# MicroMod_Asset_Tracker_Firmware_Update_T.net
KiCad netlist of a schematic drawn in EAGLE
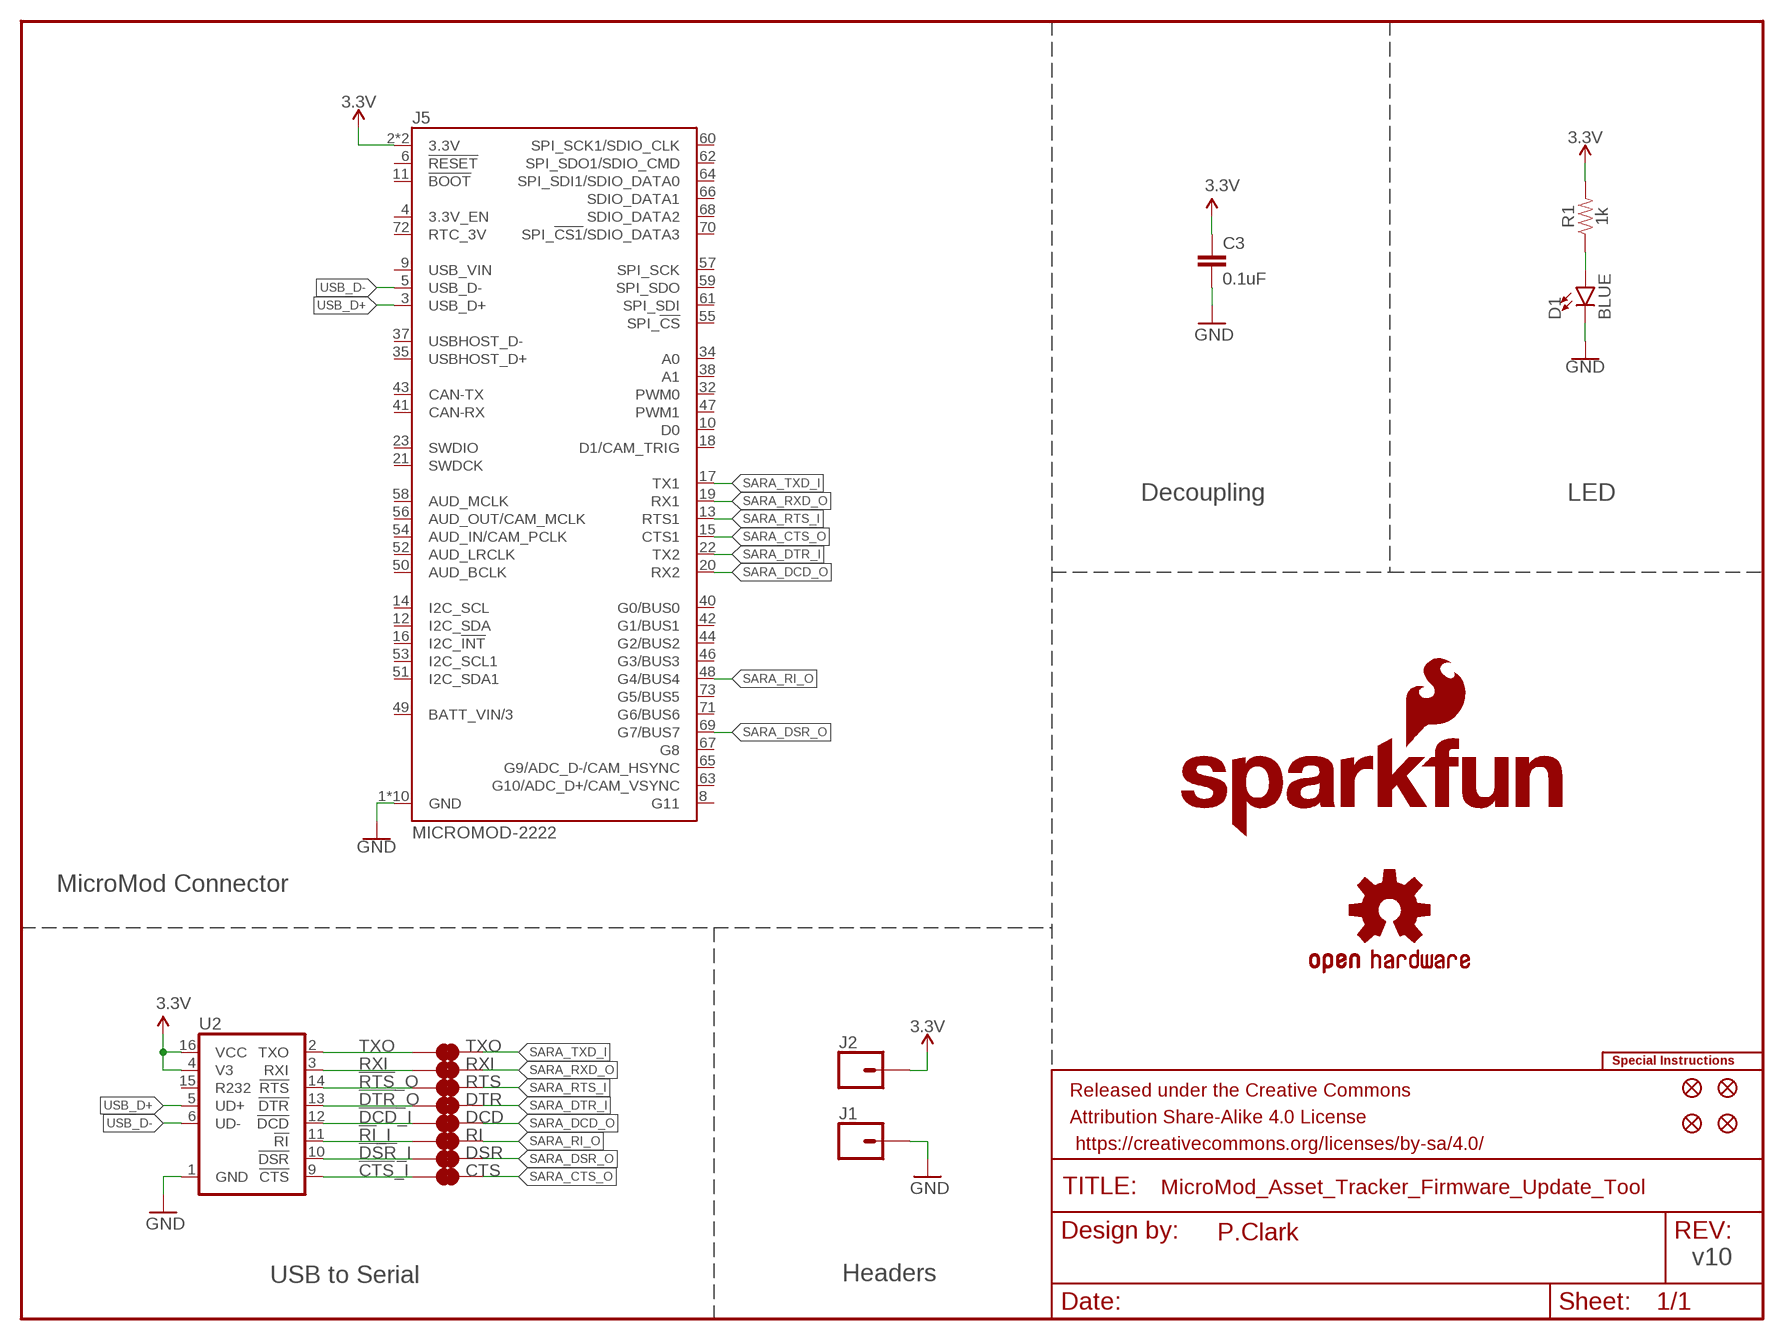
[diagram p0: schematic, sheet 1]

(export (version "E")
  (design (tool "Eeschema 10.0.6"))
  (components
    (comp (ref "C3")
      (value "0.1uF")
      (footprint "eagle-import:0603")
      (libsource (lib "eagle-import") (part "0.1UF-0603-25V-5%"))
    )
    (comp (ref "CTS")
      (value "JUMPER-COMBO_2_NC_TRACE")
      (footprint "eagle-import:COMBO-JUMPER_2_NC_TRACE")
      (libsource (lib "eagle-import") (part "JUMPER-COMBO_2_NC_TRACE"))
    )
    (comp (ref "D1")
      (value "BLUE")
      (footprint "eagle-import:LED-0603")
      (libsource (lib "eagle-import") (part "LED-BLUE0603"))
    )
    (comp (ref "DCD")
      (value "JUMPER-COMBO_2_NC_TRACE")
      (footprint "eagle-import:COMBO-JUMPER_2_NC_TRACE")
      (libsource (lib "eagle-import") (part "JUMPER-COMBO_2_NC_TRACE"))
    )
    (comp (ref "DSR")
      (value "JUMPER-COMBO_2_NC_TRACE")
      (footprint "eagle-import:COMBO-JUMPER_2_NC_TRACE")
      (libsource (lib "eagle-import") (part "JUMPER-COMBO_2_NC_TRACE"))
    )
    (comp (ref "DTR")
      (value "JUMPER-COMBO_2_NC_TRACE")
      (footprint "eagle-import:COMBO-JUMPER_2_NC_TRACE")
      (libsource (lib "eagle-import") (part "JUMPER-COMBO_2_NC_TRACE"))
    )
    (comp (ref "FRAME1")
      (value "FRAME-LETTER")
      (footprint "eagle-import:CREATIVE_COMMONS")
      (libsource (lib "eagle-import") (part "FRAME-LETTER"))
    )
    (comp (ref "J1")
      (value "CONN_01PTH_NO_SILK_YES_STOP")
      (footprint "eagle-import:1X01_NO_SILK")
      (libsource (lib "eagle-import") (part "CONN_01PTH_NO_SILK_YES_STOP"))
    )
    (comp (ref "J2")
      (value "CONN_01PTH_NO_SILK_YES_STOP")
      (footprint "eagle-import:1X01_NO_SILK")
      (libsource (lib "eagle-import") (part "CONN_01PTH_NO_SILK_YES_STOP"))
    )
    (comp (ref "J5")
      (value "MICROMOD-2222")
      (footprint "eagle-import:M.2-CARD-E-22")
      (libsource (lib "eagle-import") (part "MICROMOD-2222"))
    )
    (comp (ref "JP3")
      (value "FIDUCIAL1X2")
      (footprint "eagle-import:FIDUCIAL-1X2")
      (libsource (lib "eagle-import") (part "FIDUCIAL1X2"))
    )
    (comp (ref "JP4")
      (value "FIDUCIAL1X2")
      (footprint "eagle-import:FIDUCIAL-1X2")
      (libsource (lib "eagle-import") (part "FIDUCIAL1X2"))
    )
    (comp (ref "JP5")
      (value "FIDUCIAL1X2")
      (footprint "eagle-import:FIDUCIAL-1X2")
      (libsource (lib "eagle-import") (part "FIDUCIAL1X2"))
    )
    (comp (ref "JP6")
      (value "FIDUCIAL1X2")
      (footprint "eagle-import:FIDUCIAL-1X2")
      (libsource (lib "eagle-import") (part "FIDUCIAL1X2"))
    )
    (comp (ref "LOGO1")
      (value "OSHW-LOGOMINI")
      (footprint "eagle-import:OSHW-LOGO-MINI")
      (libsource (lib "eagle-import") (part "OSHW-LOGOMINI"))
    )
    (comp (ref "LOGO2")
      (value "SPECIAL_INSTRUCTIONS-ORDERING")
      (footprint "eagle-import:ORDERING_INSTRUCTIONS")
      (libsource (lib "eagle-import") (part "SPECIAL_INSTRUCTIONS-ORDERING"))
    )
    (comp (ref "LOGO3")
      (value "SFE_LOGO_NAME_FLAME.1_INCH")
      (footprint "eagle-import:SFE_LOGO_NAME_FLAME_.1")
      (libsource (lib "eagle-import") (part "SFE_LOGO_NAME_FLAME.1_INCH"))
    )
    (comp (ref "R1")
      (value "1k")
      (footprint "eagle-import:0603")
      (libsource (lib "eagle-import") (part "1KOHM-0603-1/10W-1%"))
    )
    (comp (ref "RI")
      (value "JUMPER-COMBO_2_NC_TRACE")
      (footprint "eagle-import:COMBO-JUMPER_2_NC_TRACE")
      (libsource (lib "eagle-import") (part "JUMPER-COMBO_2_NC_TRACE"))
    )
    (comp (ref "RTS")
      (value "JUMPER-COMBO_2_NC_TRACE")
      (footprint "eagle-import:COMBO-JUMPER_2_NC_TRACE")
      (libsource (lib "eagle-import") (part "JUMPER-COMBO_2_NC_TRACE"))
    )
    (comp (ref "RXI")
      (value "JUMPER-COMBO_2_NC_TRACE")
      (footprint "eagle-import:COMBO-JUMPER_2_NC_TRACE")
      (libsource (lib "eagle-import") (part "JUMPER-COMBO_2_NC_TRACE"))
    )
    (comp (ref "TXO")
      (value "JUMPER-COMBO_2_NC_TRACE")
      (footprint "eagle-import:COMBO-JUMPER_2_NC_TRACE")
      (libsource (lib "eagle-import") (part "JUMPER-COMBO_2_NC_TRACE"))
    )
    (comp (ref "U2")
      (value "CH340C")
      (footprint "eagle-import:SO016")
      (libsource (lib "eagle-import") (part "CH340C"))
    )
  )
  (nets
    (net (code "1") (name "/RXI") (class "Default")
      (node (ref "RXI") (pin "1") (pinfunction "1_1") (pintype "passive"))
      (node (ref "RXI") (pin "3") (pinfunction "1_3") (pintype "passive"))
      (node (ref "U2") (pin "3") (pinfunction "RXI_3") (pintype "bidirectional"))
    )
    (net (code "2") (name "/TXO") (class "Default")
      (node (ref "TXO") (pin "1") (pinfunction "1_1") (pintype "passive"))
      (node (ref "TXO") (pin "3") (pinfunction "1_3") (pintype "passive"))
      (node (ref "U2") (pin "2") (pinfunction "TXO_2") (pintype "bidirectional"))
    )
    (net (code "3") (name "/~{CTS}_I") (class "Default")
      (node (ref "CTS") (pin "1") (pinfunction "1_1") (pintype "passive"))
      (node (ref "CTS") (pin "3") (pinfunction "1_3") (pintype "passive"))
      (node (ref "U2") (pin "9") (pinfunction "~{CTS}_9") (pintype "bidirectional"))
    )
    (net (code "4") (name "/~{DCD}_I") (class "Default")
      (node (ref "DCD") (pin "1") (pinfunction "1_1") (pintype "passive"))
      (node (ref "DCD") (pin "3") (pinfunction "1_3") (pintype "passive"))
      (node (ref "U2") (pin "12") (pinfunction "~{DCD}_12") (pintype "bidirectional"))
    )
    (net (code "5") (name "/~{DSR}_I") (class "Default")
      (node (ref "DSR") (pin "1") (pinfunction "1_1") (pintype "passive"))
      (node (ref "DSR") (pin "3") (pinfunction "1_3") (pintype "passive"))
      (node (ref "U2") (pin "10") (pinfunction "~{DSR}_10") (pintype "bidirectional"))
    )
    (net (code "6") (name "/~{DTR}_O") (class "Default")
      (node (ref "DTR") (pin "1") (pinfunction "1_1") (pintype "passive"))
      (node (ref "DTR") (pin "3") (pinfunction "1_3") (pintype "passive"))
      (node (ref "U2") (pin "13") (pinfunction "~{DTR}_13") (pintype "bidirectional"))
    )
    (net (code "7") (name "/~{RI}_I") (class "Default")
      (node (ref "RI") (pin "1") (pinfunction "1_1") (pintype "passive"))
      (node (ref "RI") (pin "3") (pinfunction "1_3") (pintype "passive"))
      (node (ref "U2") (pin "11") (pinfunction "~{RI}_11") (pintype "bidirectional"))
    )
    (net (code "8") (name "/~{RTS}_O") (class "Default")
      (node (ref "RTS") (pin "1") (pinfunction "1_1") (pintype "passive"))
      (node (ref "RTS") (pin "3") (pinfunction "1_3") (pintype "passive"))
      (node (ref "U2") (pin "14") (pinfunction "~{RTS}_14") (pintype "bidirectional"))
    )
    (net (code "9") (name "3.3V") (class "Default")
      (node (ref "C3") (pin "1") (pinfunction "1_1") (pintype "passive"))
      (node (ref "J2") (pin "1") (pinfunction "1_1") (pintype "passive"))
      (node (ref "J5") (pin "2") (pinfunction "3.3V_2") (pintype "bidirectional"))
      (node (ref "J5") (pin "74") (pinfunction "3.3V_74") (pintype "bidirectional"))
      (node (ref "R1") (pin "2") (pinfunction "2_2") (pintype "passive"))
      (node (ref "U2") (pin "16") (pinfunction "VCC_16") (pintype "bidirectional"))
      (node (ref "U2") (pin "4") (pinfunction "V3_4") (pintype "bidirectional"))
    )
    (net (code "10") (name "GND") (class "Default")
      (node (ref "C3") (pin "2") (pinfunction "2_2") (pintype "passive"))
      (node (ref "D1") (pin "C") (pinfunction "C_C") (pintype "passive"))
      (node (ref "J1") (pin "1") (pinfunction "1_1") (pintype "passive"))
      (node (ref "J5") (pin "1") (pinfunction "GND_1") (pintype "bidirectional"))
      (node (ref "J5") (pin "33") (pinfunction "GND_33") (pintype "bidirectional"))
      (node (ref "J5") (pin "36") (pinfunction "GND_36") (pintype "bidirectional"))
      (node (ref "J5") (pin "39") (pinfunction "GND_39") (pintype "bidirectional"))
      (node (ref "J5") (pin "45") (pinfunction "GND_45") (pintype "bidirectional"))
      (node (ref "J5") (pin "7") (pinfunction "GND_7") (pintype "bidirectional"))
      (node (ref "J5") (pin "75") (pinfunction "GND_75") (pintype "bidirectional"))
      (node (ref "J5") (pin "GND1") (pinfunction "GND_GND1") (pintype "bidirectional"))
      (node (ref "J5") (pin "GND2") (pinfunction "GND_GND2") (pintype "bidirectional"))
      (node (ref "J5") (pin "GND3") (pinfunction "GND_GND3") (pintype "bidirectional"))
      (node (ref "U2") (pin "1") (pinfunction "GND_1") (pintype "bidirectional"))
    )
    (net (code "11") (name "Net-(D1-PadA)") (class "Default")
      (node (ref "D1") (pin "A") (pinfunction "A_A") (pintype "passive"))
      (node (ref "R1") (pin "1") (pinfunction "1_1") (pintype "passive"))
    )
    (net (code "12") (name "SARA_CTS_O") (class "Default")
      (node (ref "CTS") (pin "2") (pinfunction "2_2") (pintype "passive"))
      (node (ref "CTS") (pin "4") (pinfunction "2_4") (pintype "passive"))
      (node (ref "J5") (pin "15") (pinfunction "CTS1_15") (pintype "bidirectional"))
    )
    (net (code "13") (name "SARA_DCD_O") (class "Default")
      (node (ref "DCD") (pin "2") (pinfunction "2_2") (pintype "passive"))
      (node (ref "DCD") (pin "4") (pinfunction "2_4") (pintype "passive"))
      (node (ref "J5") (pin "20") (pinfunction "RX2_20") (pintype "bidirectional"))
    )
    (net (code "14") (name "SARA_DSR_O") (class "Default")
      (node (ref "DSR") (pin "2") (pinfunction "2_2") (pintype "passive"))
      (node (ref "DSR") (pin "4") (pinfunction "2_4") (pintype "passive"))
      (node (ref "J5") (pin "69") (pinfunction "G7/BUS7_69") (pintype "bidirectional"))
    )
    (net (code "15") (name "SARA_DTR_I") (class "Default")
      (node (ref "DTR") (pin "2") (pinfunction "2_2") (pintype "passive"))
      (node (ref "DTR") (pin "4") (pinfunction "2_4") (pintype "passive"))
      (node (ref "J5") (pin "22") (pinfunction "TX2_22") (pintype "bidirectional"))
    )
    (net (code "16") (name "SARA_RI_O") (class "Default")
      (node (ref "J5") (pin "48") (pinfunction "G4/BUS4_48") (pintype "bidirectional"))
      (node (ref "RI") (pin "2") (pinfunction "2_2") (pintype "passive"))
      (node (ref "RI") (pin "4") (pinfunction "2_4") (pintype "passive"))
    )
    (net (code "17") (name "SARA_RTS_I") (class "Default")
      (node (ref "J5") (pin "13") (pinfunction "RTS1_13") (pintype "bidirectional"))
      (node (ref "RTS") (pin "2") (pinfunction "2_2") (pintype "passive"))
      (node (ref "RTS") (pin "4") (pinfunction "2_4") (pintype "passive"))
    )
    (net (code "18") (name "SARA_RXD_O") (class "Default")
      (node (ref "J5") (pin "19") (pinfunction "RX1_19") (pintype "bidirectional"))
      (node (ref "RXI") (pin "2") (pinfunction "2_2") (pintype "passive"))
      (node (ref "RXI") (pin "4") (pinfunction "2_4") (pintype "passive"))
    )
    (net (code "19") (name "SARA_TXD_I") (class "Default")
      (node (ref "J5") (pin "17") (pinfunction "TX1_17") (pintype "bidirectional"))
      (node (ref "TXO") (pin "2") (pinfunction "2_2") (pintype "passive"))
      (node (ref "TXO") (pin "4") (pinfunction "2_4") (pintype "passive"))
    )
    (net (code "20") (name "USB_D+") (class "Default")
      (node (ref "J5") (pin "3") (pinfunction "USB_D+_3") (pintype "bidirectional"))
      (node (ref "U2") (pin "5") (pinfunction "UD+_5") (pintype "bidirectional"))
    )
    (net (code "21") (name "USB_D-") (class "Default")
      (node (ref "J5") (pin "5") (pinfunction "USB_D-_5") (pintype "bidirectional"))
      (node (ref "U2") (pin "6") (pinfunction "UD-_6") (pintype "bidirectional"))
    )
    (net (code "22") (name "unconnected-(J5-3.3V_EN-Pad4)") (class "Default")
      (node (ref "J5") (pin "4") (pinfunction "3.3V_EN_4") (pintype "bidirectional"))
    )
    (net (code "23") (name "unconnected-(J5-A0-Pad34)") (class "Default")
      (node (ref "J5") (pin "34") (pinfunction "A0_34") (pintype "bidirectional"))
    )
    (net (code "24") (name "unconnected-(J5-A1-Pad38)") (class "Default")
      (node (ref "J5") (pin "38") (pinfunction "A1_38") (pintype "bidirectional"))
    )
    (net (code "25") (name "unconnected-(J5-AUD_BCLK-Pad50)") (class "Default")
      (node (ref "J5") (pin "50") (pinfunction "AUD_BCLK_50") (pintype "bidirectional"))
    )
    (net (code "26") (name "unconnected-(J5-AUD_IN{slash}CAM_PCLK-Pad54)") (class "Default")
      (node (ref "J5") (pin "54") (pinfunction "AUD_IN/CAM_PCLK_54") (pintype "bidirectional"))
    )
    (net (code "27") (name "unconnected-(J5-AUD_LRCLK-Pad52)") (class "Default")
      (node (ref "J5") (pin "52") (pinfunction "AUD_LRCLK_52") (pintype "bidirectional"))
    )
    (net (code "28") (name "unconnected-(J5-AUD_MCLK-Pad58)") (class "Default")
      (node (ref "J5") (pin "58") (pinfunction "AUD_MCLK_58") (pintype "bidirectional"))
    )
    (net (code "29") (name "unconnected-(J5-AUD_OUT{slash}CAM_MCLK-Pad56)") (class "Default")
      (node (ref "J5") (pin "56") (pinfunction "AUD_OUT/CAM_MCLK_56") (pintype "bidirectional"))
    )
    (net (code "30") (name "unconnected-(J5-BATT_VIN{slash}3-Pad49)") (class "Default")
      (node (ref "J5") (pin "49") (pinfunction "BATT_VIN/3_49") (pintype "bidirectional"))
    )
    (net (code "31") (name "unconnected-(J5-CAN-RX-Pad41)") (class "Default")
      (node (ref "J5") (pin "41") (pinfunction "CAN-RX_41") (pintype "bidirectional"))
    )
    (net (code "32") (name "unconnected-(J5-CAN-TX-Pad43)") (class "Default")
      (node (ref "J5") (pin "43") (pinfunction "CAN-TX_43") (pintype "bidirectional"))
    )
    (net (code "33") (name "unconnected-(J5-D0-Pad10)") (class "Default")
      (node (ref "J5") (pin "10") (pinfunction "D0_10") (pintype "bidirectional"))
    )
    (net (code "34") (name "unconnected-(J5-D1{slash}CAM_TRIG-Pad18)") (class "Default")
      (node (ref "J5") (pin "18") (pinfunction "D1/CAM_TRIG_18") (pintype "bidirectional"))
    )
    (net (code "35") (name "unconnected-(J5-G0{slash}BUS0-Pad40)") (class "Default")
      (node (ref "J5") (pin "40") (pinfunction "G0/BUS0_40") (pintype "bidirectional"))
    )
    (net (code "36") (name "unconnected-(J5-G1{slash}BUS1-Pad42)") (class "Default")
      (node (ref "J5") (pin "42") (pinfunction "G1/BUS1_42") (pintype "bidirectional"))
    )
    (net (code "37") (name "unconnected-(J5-G2{slash}BUS2-Pad44)") (class "Default")
      (node (ref "J5") (pin "44") (pinfunction "G2/BUS2_44") (pintype "bidirectional"))
    )
    (net (code "38") (name "unconnected-(J5-G3{slash}BUS3-Pad46)") (class "Default")
      (node (ref "J5") (pin "46") (pinfunction "G3/BUS3_46") (pintype "bidirectional"))
    )
    (net (code "39") (name "unconnected-(J5-G5{slash}BUS5-Pad73)") (class "Default")
      (node (ref "J5") (pin "73") (pinfunction "G5/BUS5_73") (pintype "bidirectional"))
    )
    (net (code "40") (name "unconnected-(J5-G6{slash}BUS6-Pad71)") (class "Default")
      (node (ref "J5") (pin "71") (pinfunction "G6/BUS6_71") (pintype "bidirectional"))
    )
    (net (code "41") (name "unconnected-(J5-G8-Pad67)") (class "Default")
      (node (ref "J5") (pin "67") (pinfunction "G8_67") (pintype "bidirectional"))
    )
    (net (code "42") (name "unconnected-(J5-G9{slash}ADC_D-{slash}CAM_HSYNC-Pad65)") (class "Default")
      (node (ref "J5") (pin "65") (pinfunction "G9/ADC_D-/CAM_HSYNC_65") (pintype "bidirectional"))
    )
    (net (code "43") (name "unconnected-(J5-G10{slash}ADC_D+{slash}CAM_VSYNC-Pad63)") (class "Default")
      (node (ref "J5") (pin "63") (pinfunction "G10/ADC_D+/CAM_VSYNC_63") (pintype "bidirectional"))
    )
    (net (code "44") (name "unconnected-(J5-G11-Pad8)") (class "Default")
      (node (ref "J5") (pin "8") (pinfunction "G11_8") (pintype "bidirectional"))
    )
    (net (code "45") (name "unconnected-(J5-I2C_SCL-Pad14)") (class "Default")
      (node (ref "J5") (pin "14") (pinfunction "I2C_SCL_14") (pintype "bidirectional"))
    )
    (net (code "46") (name "unconnected-(J5-I2C_SCL1-Pad53)") (class "Default")
      (node (ref "J5") (pin "53") (pinfunction "I2C_SCL1_53") (pintype "bidirectional"))
    )
    (net (code "47") (name "unconnected-(J5-I2C_SDA-Pad12)") (class "Default")
      (node (ref "J5") (pin "12") (pinfunction "I2C_SDA_12") (pintype "bidirectional"))
    )
    (net (code "48") (name "unconnected-(J5-I2C_SDA1-Pad51)") (class "Default")
      (node (ref "J5") (pin "51") (pinfunction "I2C_SDA1_51") (pintype "bidirectional"))
    )
    (net (code "49") (name "unconnected-(J5-I2C_~{INT}-Pad16)") (class "Default")
      (node (ref "J5") (pin "16") (pinfunction "I2C_~{INT}_16") (pintype "bidirectional"))
    )
    (net (code "50") (name "unconnected-(J5-PWM0-Pad32)") (class "Default")
      (node (ref "J5") (pin "32") (pinfunction "PWM0_32") (pintype "bidirectional"))
    )
    (net (code "51") (name "unconnected-(J5-PWM1-Pad47)") (class "Default")
      (node (ref "J5") (pin "47") (pinfunction "PWM1_47") (pintype "bidirectional"))
    )
    (net (code "52") (name "unconnected-(J5-RTC_3V-Pad72)") (class "Default")
      (node (ref "J5") (pin "72") (pinfunction "RTC_3V_72") (pintype "bidirectional"))
    )
    (net (code "53") (name "unconnected-(J5-SDIO_DATA1-Pad66)") (class "Default")
      (node (ref "J5") (pin "66") (pinfunction "SDIO_DATA1_66") (pintype "bidirectional"))
    )
    (net (code "54") (name "unconnected-(J5-SDIO_DATA2-Pad68)") (class "Default")
      (node (ref "J5") (pin "68") (pinfunction "SDIO_DATA2_68") (pintype "bidirectional"))
    )
    (net (code "55") (name "unconnected-(J5-SPI_SCK-Pad57)") (class "Default")
      (node (ref "J5") (pin "57") (pinfunction "SPI_SCK_57") (pintype "bidirectional"))
    )
    (net (code "56") (name "unconnected-(J5-SPI_SCK1{slash}SDIO_CLK-Pad60)") (class "Default")
      (node (ref "J5") (pin "60") (pinfunction "SPI_SCK1/SDIO_CLK_60") (pintype "bidirectional"))
    )
    (net (code "57") (name "unconnected-(J5-SPI_SDI-Pad61)") (class "Default")
      (node (ref "J5") (pin "61") (pinfunction "SPI_SDI_61") (pintype "bidirectional"))
    )
    (net (code "58") (name "unconnected-(J5-SPI_SDI1{slash}SDIO_DATA0-Pad64)") (class "Default")
      (node (ref "J5") (pin "64") (pinfunction "SPI_SDI1/SDIO_DATA0_64") (pintype "bidirectional"))
    )
    (net (code "59") (name "unconnected-(J5-SPI_SDO-Pad59)") (class "Default")
      (node (ref "J5") (pin "59") (pinfunction "SPI_SDO_59") (pintype "bidirectional"))
    )
    (net (code "60") (name "unconnected-(J5-SPI_SDO1{slash}SDIO_CMD-Pad62)") (class "Default")
      (node (ref "J5") (pin "62") (pinfunction "SPI_SDO1/SDIO_CMD_62") (pintype "bidirectional"))
    )
    (net (code "61") (name "unconnected-(J5-SPI_~{CS1}{slash}SDIO_DATA3-Pad70)") (class "Default")
      (node (ref "J5") (pin "70") (pinfunction "SPI_~{CS1}/SDIO_DATA3_70") (pintype "bidirectional"))
    )
    (net (code "62") (name "unconnected-(J5-SPI_~{CS}-Pad55)") (class "Default")
      (node (ref "J5") (pin "55") (pinfunction "SPI_~{CS}_55") (pintype "bidirectional"))
    )
    (net (code "63") (name "unconnected-(J5-SWDCK-Pad21)") (class "Default")
      (node (ref "J5") (pin "21") (pinfunction "SWDCK_21") (pintype "bidirectional"))
    )
    (net (code "64") (name "unconnected-(J5-SWDIO-Pad23)") (class "Default")
      (node (ref "J5") (pin "23") (pinfunction "SWDIO_23") (pintype "bidirectional"))
    )
    (net (code "65") (name "unconnected-(J5-USBHOST_D+-Pad35)") (class "Default")
      (node (ref "J5") (pin "35") (pinfunction "USBHOST_D+_35") (pintype "bidirectional"))
    )
    (net (code "66") (name "unconnected-(J5-USBHOST_D--Pad37)") (class "Default")
      (node (ref "J5") (pin "37") (pinfunction "USBHOST_D-_37") (pintype "bidirectional"))
    )
    (net (code "67") (name "unconnected-(J5-USB_VIN-Pad9)") (class "Default")
      (node (ref "J5") (pin "9") (pinfunction "USB_VIN_9") (pintype "bidirectional"))
    )
    (net (code "68") (name "unconnected-(J5-~{BOOT}-Pad11)") (class "Default")
      (node (ref "J5") (pin "11") (pinfunction "~{BOOT}_11") (pintype "bidirectional"))
    )
    (net (code "69") (name "unconnected-(J5-~{RESET}-Pad6)") (class "Default")
      (node (ref "J5") (pin "6") (pinfunction "~{RESET}_6") (pintype "bidirectional"))
    )
    (net (code "70") (name "unconnected-(U2-R232-Pad15)") (class "Default")
      (node (ref "U2") (pin "15") (pinfunction "R232_15") (pintype "bidirectional"))
    )
  )
)
